# Combined_parts.net
KiCad netlist of a schematic drawn in Altium Designer
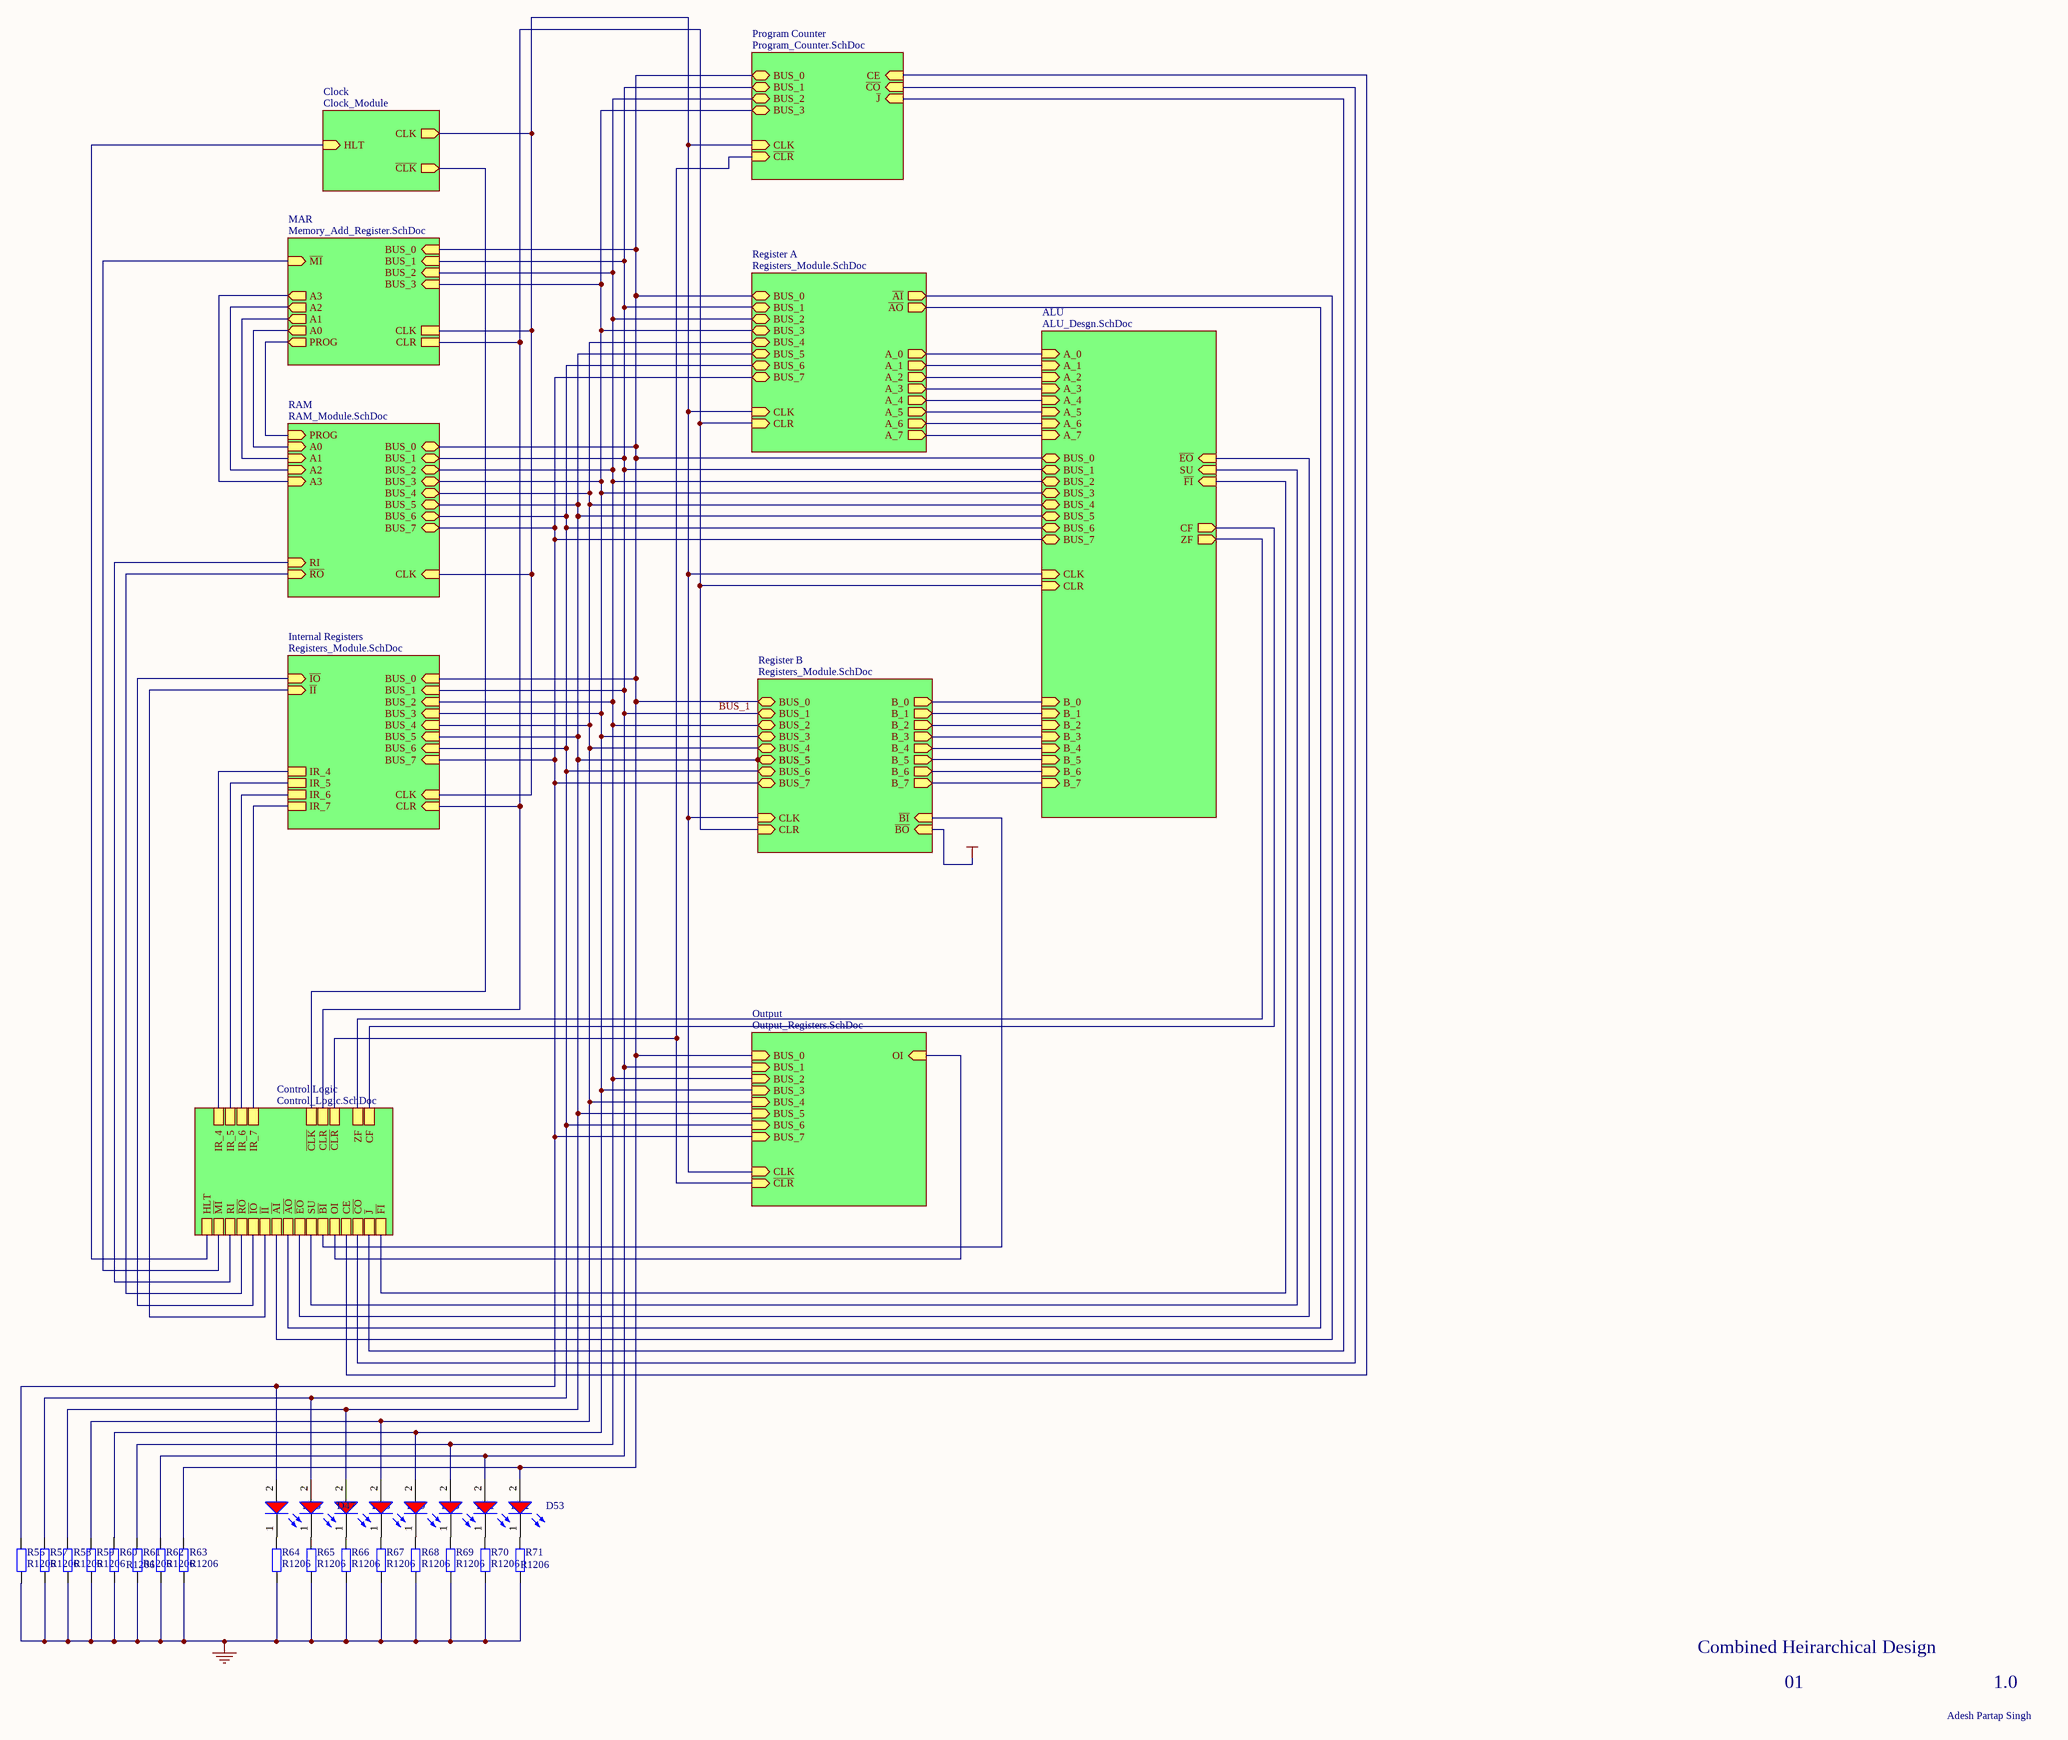
[diagram p0: Combined_parts.SchDoc]

(export (version "E")
  (design (tool "Eeschema 10.0.6"))
  (components
    (comp (ref "D46")
      (value "151053RS03000")
      (footprint "WL-TMRW_D5.8H11.7")
      (libsource (lib "8BIT_COMP_LIB") (part "CMP-1489-00007-2"))
    )
    (comp (ref "D47")
      (value "151053RS03000")
      (footprint "WL-TMRW_D5.8H11.7")
      (libsource (lib "8BIT_COMP_LIB") (part "CMP-1489-00007-2"))
    )
    (comp (ref "D48")
      (value "151053RS03000")
      (footprint "WL-TMRW_D5.8H11.7")
      (libsource (lib "8BIT_COMP_LIB") (part "CMP-1489-00007-2"))
    )
    (comp (ref "D49")
      (value "151053RS03000")
      (footprint "WL-TMRW_D5.8H11.7")
      (libsource (lib "8BIT_COMP_LIB") (part "CMP-1489-00007-2"))
    )
    (comp (ref "D50")
      (value "151053RS03000")
      (footprint "WL-TMRW_D5.8H11.7")
      (libsource (lib "8BIT_COMP_LIB") (part "CMP-1489-00007-2"))
    )
    (comp (ref "D51")
      (value "151053RS03000")
      (footprint "WL-TMRW_D5.8H11.7")
      (libsource (lib "8BIT_COMP_LIB") (part "CMP-1489-00007-2"))
    )
    (comp (ref "D52")
      (value "151053RS03000")
      (footprint "WL-TMRW_D5.8H11.7")
      (libsource (lib "8BIT_COMP_LIB") (part "CMP-1489-00007-2"))
    )
    (comp (ref "D53")
      (value "151053RS03000")
      (footprint "WL-TMRW_D5.8H11.7")
      (libsource (lib "8BIT_COMP_LIB") (part "CMP-1489-00007-2"))
    )
    (comp (ref "R56")
      (value "R1206")
      (footprint "RES_1206")
      (description "Resistor SMD 1206")
      (libsource (lib "Schematic-Lib-PhilsLab") (part "RES_1206"))
    )
    (comp (ref "R57")
      (value "R1206")
      (footprint "RES_1206")
      (description "Resistor SMD 1206")
      (libsource (lib "Schematic-Lib-PhilsLab") (part "RES_1206"))
    )
    (comp (ref "R58")
      (value "R1206")
      (footprint "RES_1206")
      (description "Resistor SMD 1206")
      (libsource (lib "Schematic-Lib-PhilsLab") (part "RES_1206"))
    )
    (comp (ref "R59")
      (value "R1206")
      (footprint "RES_1206")
      (description "Resistor SMD 1206")
      (libsource (lib "Schematic-Lib-PhilsLab") (part "RES_1206"))
    )
    (comp (ref "R60")
      (value "R1206")
      (footprint "RES_1206")
      (description "Resistor SMD 1206")
      (libsource (lib "Schematic-Lib-PhilsLab") (part "RES_1206"))
    )
    (comp (ref "R61")
      (value "R1206")
      (footprint "RES_1206")
      (description "Resistor SMD 1206")
      (libsource (lib "Schematic-Lib-PhilsLab") (part "RES_1206"))
    )
    (comp (ref "R62")
      (value "R1206")
      (footprint "RES_1206")
      (description "Resistor SMD 1206")
      (libsource (lib "Schematic-Lib-PhilsLab") (part "RES_1206"))
    )
    (comp (ref "R63")
      (value "R1206")
      (footprint "RES_1206")
      (description "Resistor SMD 1206")
      (libsource (lib "Schematic-Lib-PhilsLab") (part "RES_1206"))
    )
    (comp (ref "R64")
      (value "R1206")
      (footprint "RES_1206")
      (description "Resistor SMD 1206")
      (libsource (lib "Schematic-Lib-PhilsLab") (part "RES_1206"))
    )
    (comp (ref "R65")
      (value "R1206")
      (footprint "RES_1206")
      (description "Resistor SMD 1206")
      (libsource (lib "Schematic-Lib-PhilsLab") (part "RES_1206"))
    )
    (comp (ref "R66")
      (value "R1206")
      (footprint "RES_1206")
      (description "Resistor SMD 1206")
      (libsource (lib "Schematic-Lib-PhilsLab") (part "RES_1206"))
    )
    (comp (ref "R67")
      (value "R1206")
      (footprint "RES_1206")
      (description "Resistor SMD 1206")
      (libsource (lib "Schematic-Lib-PhilsLab") (part "RES_1206"))
    )
    (comp (ref "R68")
      (value "R1206")
      (footprint "RES_1206")
      (description "Resistor SMD 1206")
      (libsource (lib "Schematic-Lib-PhilsLab") (part "RES_1206"))
    )
    (comp (ref "R69")
      (value "R1206")
      (footprint "RES_1206")
      (description "Resistor SMD 1206")
      (libsource (lib "Schematic-Lib-PhilsLab") (part "RES_1206"))
    )
    (comp (ref "R70")
      (value "R1206")
      (footprint "RES_1206")
      (description "Resistor SMD 1206")
      (libsource (lib "Schematic-Lib-PhilsLab") (part "RES_1206"))
    )
    (comp (ref "R71")
      (value "R1206")
      (footprint "RES_1206")
      (description "Resistor SMD 1206")
      (libsource (lib "Schematic-Lib-PhilsLab") (part "RES_1206"))
    )
  )
  (nets
    (net (code "13") (name "/BUS_0") (class "Default")
      (node (ref "D53") (pin "2") (pinfunction "A_2") (pintype "passive"))
      (node (ref "R63") (pin "2") (pinfunction "2_2") (pintype "passive"))
    )
    (net (code "14") (name "/BUS_1") (class "Default")
      (node (ref "D52") (pin "2") (pinfunction "A_2") (pintype "passive"))
      (node (ref "R62") (pin "2") (pinfunction "2_2") (pintype "passive"))
    )
    (net (code "15") (name "/BUS_2") (class "Default")
      (node (ref "D51") (pin "2") (pinfunction "A_2") (pintype "passive"))
      (node (ref "R61") (pin "2") (pinfunction "2_2") (pintype "passive"))
    )
    (net (code "16") (name "/BUS_3") (class "Default")
      (node (ref "D50") (pin "2") (pinfunction "A_2") (pintype "passive"))
      (node (ref "R60") (pin "2") (pinfunction "2_2") (pintype "passive"))
    )
    (net (code "17") (name "/BUS_4") (class "Default")
      (node (ref "D49") (pin "2") (pinfunction "A_2") (pintype "passive"))
      (node (ref "R59") (pin "2") (pinfunction "2_2") (pintype "passive"))
    )
    (net (code "18") (name "/BUS_5") (class "Default")
      (node (ref "D48") (pin "2") (pinfunction "A_2") (pintype "passive"))
      (node (ref "R58") (pin "2") (pinfunction "2_2") (pintype "passive"))
    )
    (net (code "19") (name "/BUS_6") (class "Default")
      (node (ref "D47") (pin "2") (pinfunction "A_2") (pintype "passive"))
      (node (ref "R57") (pin "2") (pinfunction "2_2") (pintype "passive"))
    )
    (net (code "20") (name "/BUS_7") (class "Default")
      (node (ref "D46") (pin "2") (pinfunction "A_2") (pintype "passive"))
      (node (ref "R56") (pin "2") (pinfunction "2_2") (pintype "passive"))
    )
    (net (code "56") (name "GND") (class "Default")
      (node (ref "R56") (pin "1") (pinfunction "1_1") (pintype "passive"))
      (node (ref "R57") (pin "1") (pinfunction "1_1") (pintype "passive"))
      (node (ref "R58") (pin "1") (pinfunction "1_1") (pintype "passive"))
      (node (ref "R59") (pin "1") (pinfunction "1_1") (pintype "passive"))
      (node (ref "R60") (pin "1") (pinfunction "1_1") (pintype "passive"))
      (node (ref "R61") (pin "1") (pinfunction "1_1") (pintype "passive"))
      (node (ref "R62") (pin "1") (pinfunction "1_1") (pintype "passive"))
      (node (ref "R63") (pin "1") (pinfunction "1_1") (pintype "passive"))
      (node (ref "R64") (pin "1") (pinfunction "1_1") (pintype "passive"))
      (node (ref "R65") (pin "1") (pinfunction "1_1") (pintype "passive"))
      (node (ref "R66") (pin "1") (pinfunction "1_1") (pintype "passive"))
      (node (ref "R67") (pin "1") (pinfunction "1_1") (pintype "passive"))
      (node (ref "R68") (pin "1") (pinfunction "1_1") (pintype "passive"))
      (node (ref "R69") (pin "1") (pinfunction "1_1") (pintype "passive"))
      (node (ref "R70") (pin "1") (pinfunction "1_1") (pintype "passive"))
      (node (ref "R71") (pin "1") (pinfunction "1_1") (pintype "passive"))
    )
    (net (code "57") (name "Net-(D46-K)") (class "Default")
      (node (ref "D46") (pin "1") (pinfunction "K_1") (pintype "passive"))
      (node (ref "R64") (pin "2") (pinfunction "2_2") (pintype "passive"))
    )
    (net (code "58") (name "Net-(D47-K)") (class "Default")
      (node (ref "D47") (pin "1") (pinfunction "K_1") (pintype "passive"))
      (node (ref "R65") (pin "2") (pinfunction "2_2") (pintype "passive"))
    )
    (net (code "59") (name "Net-(D48-K)") (class "Default")
      (node (ref "D48") (pin "1") (pinfunction "K_1") (pintype "passive"))
      (node (ref "R66") (pin "2") (pinfunction "2_2") (pintype "passive"))
    )
    (net (code "60") (name "Net-(D49-K)") (class "Default")
      (node (ref "D49") (pin "1") (pinfunction "K_1") (pintype "passive"))
      (node (ref "R67") (pin "2") (pinfunction "2_2") (pintype "passive"))
    )
    (net (code "61") (name "Net-(D50-K)") (class "Default")
      (node (ref "D50") (pin "1") (pinfunction "K_1") (pintype "passive"))
      (node (ref "R68") (pin "2") (pinfunction "2_2") (pintype "passive"))
    )
    (net (code "62") (name "Net-(D51-K)") (class "Default")
      (node (ref "D51") (pin "1") (pinfunction "K_1") (pintype "passive"))
      (node (ref "R69") (pin "2") (pinfunction "2_2") (pintype "passive"))
    )
    (net (code "63") (name "Net-(D52-K)") (class "Default")
      (node (ref "D52") (pin "1") (pinfunction "K_1") (pintype "passive"))
      (node (ref "R70") (pin "2") (pinfunction "2_2") (pintype "passive"))
    )
    (net (code "64") (name "Net-(D53-K)") (class "Default")
      (node (ref "D53") (pin "1") (pinfunction "K_1") (pintype "passive"))
      (node (ref "R71") (pin "2") (pinfunction "2_2") (pintype "passive"))
    )
  )
)
